# PowerGroup.net
KiCad netlist of a schematic drawn in Altium Designer
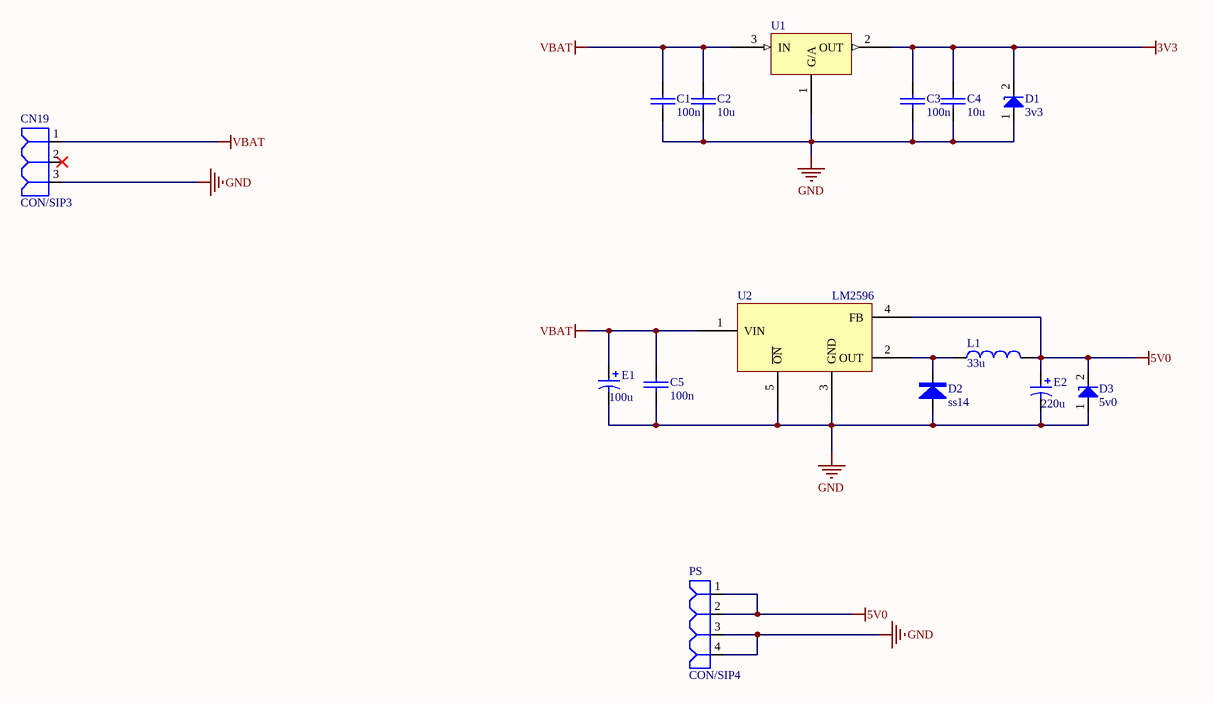
[diagram p0: PowerGroup.SchDoc]

(export (version "E")
  (design (tool "Eeschema 10.0.6"))
  (components
    (comp (ref "C1")
      (value "100n")
      (footprint "C0402")
      (description "电容")
      (libsource (lib "LQ_Integrated_Library") (part "Capacitor"))
    )
    (comp (ref "C2")
      (value "10u")
      (footprint "C0402")
      (description "电容")
      (libsource (lib "LQ_Integrated_Library") (part "Capacitor"))
    )
    (comp (ref "C3")
      (value "100n")
      (footprint "C0402")
      (description "电容")
      (libsource (lib "LQ_Integrated_Library") (part "Capacitor"))
    )
    (comp (ref "C4")
      (value "10u")
      (footprint "C0402")
      (description "电容")
      (libsource (lib "LQ_Integrated_Library") (part "Capacitor"))
    )
    (comp (ref "C5")
      (value "100n")
      (footprint "C0603")
      (description "电容")
      (libsource (lib "LQ_Integrated_Library") (part "Capacitor"))
    )
    (comp (ref "CN19")
      (value "CON/SIP3")
      (footprint "HDR1X3")
      (libsource (lib "LQ_Integrated_Library") (part "CON/SIP3"))
    )
    (comp (ref "D1")
      (value "3v3")
      (footprint "D1206")
      (libsource (lib "LQ_Integrated_Library") (part "DIODE稳压"))
    )
    (comp (ref "D2")
      (value "ss14")
      (footprint "DO-214")
      (description "二极管")
      (libsource (lib "LQ_Integrated_Library") (part "DIODE"))
    )
    (comp (ref "D3")
      (value "5v0")
      (footprint "D1206")
      (libsource (lib "LQ_Integrated_Library") (part "DIODE稳压"))
    )
    (comp (ref "E1")
      (value "100u")
      (footprint "CAP-E SMD-A")
      (description "极性电容")
      (libsource (lib "LQ_Integrated_Library") (part "Capacitor-Polarity"))
    )
    (comp (ref "E2")
      (value "220u")
      (footprint "CAP-E SMD-A")
      (description "极性电容")
      (libsource (lib "LQ_Integrated_Library") (part "Capacitor-Polarity"))
    )
    (comp (ref "L1")
      (value "33u")
      (footprint "L7X7")
      (description "Inductor")
      (libsource (lib "LQ_Integrated_Library") (part "INDUCTOR"))
    )
    (comp (ref "PS")
      (value "CON/SIP4")
      (footprint "HDR1X4")
      (libsource (lib "LQ_Integrated_Library") (part "CON/SIP4"))
    )
    (comp (ref "U1")
      (value "AMS1117-XX")
      (footprint "SOT223")
      (description "稳压芯片")
      (libsource (lib "LQ_Integrated_Library") (part "AMS1117-XX"))
    )
    (comp (ref "U2")
      (value "LM2596")
      (footprint "TO263S")
      (description "DCDCBUCK")
      (libsource (lib "LQ_Integrated_Library") (part "LM2596"))
    )
  )
  (nets
    (net (code "1") (name "3V3") (class "Default")
      (node (ref "C3") (pin "2") (pinfunction "2_2") (pintype "passive"))
      (node (ref "C4") (pin "2") (pinfunction "2_2") (pintype "passive"))
      (node (ref "D1") (pin "2") (pintype "passive"))
      (node (ref "U1") (pin "2") (pinfunction "OUT_2") (pintype "output"))
    )
    (net (code "2") (name "5V0") (class "Default")
      (node (ref "D3") (pin "2") (pintype "passive"))
      (node (ref "E2") (pin "1") (pinfunction "1_1") (pintype "passive"))
      (node (ref "L1") (pin "2") (pinfunction "2_2") (pintype "passive"))
      (node (ref "PS") (pin "1") (pintype "passive"))
      (node (ref "PS") (pin "2") (pintype "passive"))
      (node (ref "U2") (pin "4") (pinfunction "FB_4") (pintype "passive"))
    )
    (net (code "3") (name "GND") (class "Default")
      (node (ref "C1") (pin "1") (pinfunction "1_1") (pintype "passive"))
      (node (ref "C2") (pin "1") (pinfunction "1_1") (pintype "passive"))
      (node (ref "C3") (pin "1") (pinfunction "1_1") (pintype "passive"))
      (node (ref "C4") (pin "1") (pinfunction "1_1") (pintype "passive"))
      (node (ref "C5") (pin "2") (pinfunction "2_2") (pintype "passive"))
      (node (ref "CN19") (pin "3") (pintype "passive"))
      (node (ref "D1") (pin "1") (pintype "passive"))
      (node (ref "D2") (pin "1") (pinfunction "A_1") (pintype "passive"))
      (node (ref "D3") (pin "1") (pintype "passive"))
      (node (ref "E1") (pin "2") (pinfunction "2_2") (pintype "passive"))
      (node (ref "E2") (pin "2") (pinfunction "2_2") (pintype "passive"))
      (node (ref "PS") (pin "3") (pintype "passive"))
      (node (ref "PS") (pin "4") (pintype "passive"))
      (node (ref "U1") (pin "1") (pinfunction "G/A_1") (pintype "passive"))
      (node (ref "U2") (pin "3") (pinfunction "GND_3") (pintype "passive"))
      (node (ref "U2") (pin "5") (pinfunction "~{ON}_5") (pintype "passive"))
    )
    (net (code "4") (name "Net-(D2-K)") (class "Default")
      (node (ref "D2") (pin "2") (pinfunction "K_2") (pintype "passive"))
      (node (ref "L1") (pin "1") (pinfunction "1_1") (pintype "passive"))
      (node (ref "U2") (pin "2") (pinfunction "OUT_2") (pintype "passive"))
    )
    (net (code "5") (name "VBAT") (class "Default")
      (node (ref "C1") (pin "2") (pinfunction "2_2") (pintype "passive"))
      (node (ref "C2") (pin "2") (pinfunction "2_2") (pintype "passive"))
      (node (ref "C5") (pin "1") (pinfunction "1_1") (pintype "passive"))
      (node (ref "CN19") (pin "1") (pintype "passive"))
      (node (ref "E1") (pin "1") (pinfunction "1_1") (pintype "passive"))
      (node (ref "U1") (pin "3") (pinfunction "IN_3") (pintype "input"))
      (node (ref "U2") (pin "1") (pinfunction "VIN_1") (pintype "passive"))
    )
    (net (code "6") (name "unconnected-(CN19-Pad2)") (class "Default")
      (node (ref "CN19") (pin "2") (pintype "passive+no_connect"))
    )
  )
)
